# OpenRing_PPG.net
KiCad netlist of a schematic drawn in Altium Designer
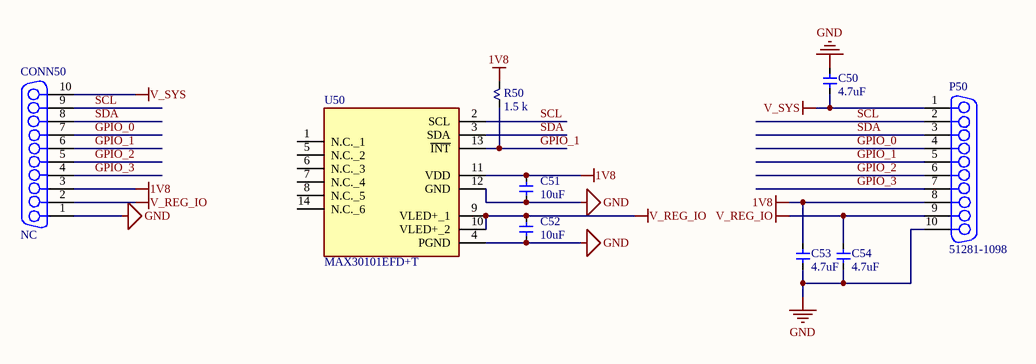
[diagram p0: OpenRing_PPG.SchDoc]

(export (version "E")
  (design (tool "Eeschema 10.0.6"))
  (components
    (comp (ref "C50")
      (value "4.7uF")
      (footprint "CAPC1005X05N")
      (description "Multilayer Ceramic Capacitor, 4.7 uF, 10 V, ± 20%, X5R, 0402 [1005 Metric]")
      (fields
        (field (name "MANUFACTURER") "Murata")
        (field (name "MANUFACTURER PART NUMBER") "GRM155R61A475MEAAD")
      )
      (libsource (lib "OpenRingComponents") (part "GRM155R61A475MEAAD"))
    )
    (comp (ref "C51")
      (value "10uF")
      (footprint "CAPC1005X05N")
      (description "Multilayer Ceramic Capacitor, 10 uF, 10 V, ± 20%, X5R, 0402 [1005 Metric]")
      (fields
        (field (name "MANUFACTURER") "Samsung")
        (field (name "MANUFACTURER PART NUMBER") "CL05A106MP5NUNC")
      )
      (libsource (lib "OpenRingComponents") (part "CL05A106MP5NUNC"))
    )
    (comp (ref "C52")
      (value "10uF")
      (footprint "CAPC1005X05N")
      (description "Multilayer Ceramic Capacitor, 10 uF, 10 V, ± 20%, X5R, 0402 [1005 Metric]")
      (fields
        (field (name "MANUFACTURER") "Samsung")
        (field (name "MANUFACTURER PART NUMBER") "CL05A106MP5NUNC")
      )
      (libsource (lib "OpenRingComponents") (part "CL05A106MP5NUNC"))
    )
    (comp (ref "C53")
      (value "4.7uF")
      (footprint "CAPC1005X05N")
      (description "Multilayer Ceramic Capacitor, 4.7 uF, 10 V, ± 20%, X5R, 0402 [1005 Metric]")
      (fields
        (field (name "MANUFACTURER") "Murata")
        (field (name "MANUFACTURER PART NUMBER") "GRM155R61A475MEAAD")
      )
      (libsource (lib "OpenRingComponents") (part "GRM155R61A475MEAAD"))
    )
    (comp (ref "C54")
      (value "4.7uF")
      (footprint "CAPC1005X05N")
      (description "Multilayer Ceramic Capacitor, 4.7 uF, 10 V, ± 20%, X5R, 0402 [1005 Metric]")
      (fields
        (field (name "MANUFACTURER") "Murata")
        (field (name "MANUFACTURER PART NUMBER") "GRM155R61A475MEAAD")
      )
      (libsource (lib "OpenRingComponents") (part "GRM155R61A475MEAAD"))
    )
    (comp (ref "CONN50")
      (value "NC")
      (footprint "51281-1098-PCB")
      (libsource (lib "Connectors") (part "51281-1098-PCB"))
    )
    (comp (ref "P50")
      (value "51281-1098")
      (footprint "51281-1098")
      (description "FFC/FPC Connector, Surface Mount, Right-Angle, Non-ZIF, Dual Contact Style")
      (fields (field (name "MANUFACTURER") "Molex"))
      (libsource (lib "Connectors") (part "51281-1098"))
    )
    (comp (ref "R50")
      (value "1.5 k")
      (footprint "RESC1005X04N")
      (description "RES SMD 1.5K OHM 1% 1/10W 0402")
      (fields
        (field (name "MANUFACTURER") "Panasonic Electronic Components")
        (field (name "MANUFACTURER PART NUMBER") "ERJ-2RKF1501X")
      )
      (libsource (lib "OpenRingComponents") (part "ERJ-2RKF1501X"))
    )
    (comp (ref "U50")
      (value "MAX30101EFD+T")
      (footprint "14-LEAD-OESIP")
      (description "High-Sensitivity Pulse Oximeter and Heart-Rate Sensor for Fitness & Healthcare")
      (fields (field (name "MANUFACTURER") "Maxim"))
      (libsource (lib "Modules") (part "MAX30101EFD+T"))
    )
  )
  (nets
    (net (code "1") (name "/GPIO_0") (class "Default")
      (node (ref "CONN50") (pin "7") (pinfunction "7_7") (pintype "passive"))
      (node (ref "P50") (pin "4") (pinfunction "4_4") (pintype "passive"))
    )
    (net (code "2") (name "/GPIO_1") (class "Default")
      (node (ref "CONN50") (pin "6") (pinfunction "6_6") (pintype "passive"))
      (node (ref "P50") (pin "5") (pinfunction "5_5") (pintype "passive"))
      (node (ref "R50") (pin "1") (pinfunction "1_1") (pintype "passive"))
      (node (ref "U50") (pin "13") (pinfunction "~{INT}_13") (pintype "passive"))
    )
    (net (code "3") (name "/GPIO_2") (class "Default")
      (node (ref "CONN50") (pin "5") (pinfunction "5_5") (pintype "passive"))
      (node (ref "P50") (pin "6") (pinfunction "6_6") (pintype "passive"))
    )
    (net (code "4") (name "/GPIO_3") (class "Default")
      (node (ref "CONN50") (pin "4") (pinfunction "4_4") (pintype "passive"))
      (node (ref "P50") (pin "7") (pinfunction "7_7") (pintype "passive"))
    )
    (net (code "5") (name "/SCL") (class "Default")
      (node (ref "CONN50") (pin "9") (pinfunction "9_9") (pintype "passive"))
      (node (ref "P50") (pin "2") (pinfunction "2_2") (pintype "passive"))
      (node (ref "U50") (pin "2") (pinfunction "SCL_2") (pintype "passive"))
    )
    (net (code "6") (name "/SDA") (class "Default")
      (node (ref "CONN50") (pin "8") (pinfunction "8_8") (pintype "passive"))
      (node (ref "P50") (pin "3") (pinfunction "3_3") (pintype "passive"))
      (node (ref "U50") (pin "3") (pinfunction "SDA_3") (pintype "passive"))
    )
    (net (code "7") (name "1V8") (class "Default")
      (node (ref "C51") (pin "2") (pinfunction "2_2") (pintype "passive"))
      (node (ref "C53") (pin "2") (pinfunction "2_2") (pintype "passive"))
      (node (ref "CONN50") (pin "3") (pinfunction "3_3") (pintype "passive"))
      (node (ref "P50") (pin "8") (pinfunction "8_8") (pintype "passive"))
      (node (ref "R50") (pin "2") (pinfunction "2_2") (pintype "passive"))
      (node (ref "U50") (pin "11") (pinfunction "VDD_11") (pintype "passive"))
    )
    (net (code "8") (name "GND") (class "Default")
      (node (ref "C50") (pin "2") (pinfunction "2_2") (pintype "passive"))
      (node (ref "C51") (pin "1") (pinfunction "1_1") (pintype "passive"))
      (node (ref "C52") (pin "2") (pinfunction "2_2") (pintype "passive"))
      (node (ref "C53") (pin "1") (pinfunction "1_1") (pintype "passive"))
      (node (ref "C54") (pin "1") (pinfunction "1_1") (pintype "passive"))
      (node (ref "CONN50") (pin "1") (pinfunction "1_1") (pintype "passive"))
      (node (ref "P50") (pin "10") (pinfunction "10_10") (pintype "passive"))
      (node (ref "U50") (pin "12") (pinfunction "GND_12") (pintype "passive"))
      (node (ref "U50") (pin "4") (pinfunction "PGND_4") (pintype "passive"))
    )
    (net (code "9") (name "V_REG_IO") (class "Default")
      (node (ref "C52") (pin "1") (pinfunction "1_1") (pintype "passive"))
      (node (ref "C54") (pin "2") (pinfunction "2_2") (pintype "passive"))
      (node (ref "CONN50") (pin "2") (pinfunction "2_2") (pintype "passive"))
      (node (ref "P50") (pin "9") (pinfunction "9_9") (pintype "passive"))
      (node (ref "U50") (pin "10") (pinfunction "VLED+_2_10") (pintype "passive"))
      (node (ref "U50") (pin "9") (pinfunction "VLED+_1_9") (pintype "passive"))
    )
    (net (code "10") (name "V_SYS") (class "Default")
      (node (ref "C50") (pin "1") (pinfunction "1_1") (pintype "passive"))
      (node (ref "CONN50") (pin "10") (pinfunction "10_10") (pintype "passive"))
      (node (ref "P50") (pin "1") (pinfunction "1_1") (pintype "passive"))
    )
    (net (code "11") (name "unconnected-(U50-N.C._1-Pad1)") (class "Default")
      (node (ref "U50") (pin "1") (pinfunction "N.C._1_1") (pintype "passive"))
    )
    (net (code "12") (name "unconnected-(U50-N.C._2-Pad5)") (class "Default")
      (node (ref "U50") (pin "5") (pinfunction "N.C._2_5") (pintype "passive"))
    )
    (net (code "13") (name "unconnected-(U50-N.C._3-Pad6)") (class "Default")
      (node (ref "U50") (pin "6") (pinfunction "N.C._3_6") (pintype "passive"))
    )
    (net (code "14") (name "unconnected-(U50-N.C._4-Pad7)") (class "Default")
      (node (ref "U50") (pin "7") (pinfunction "N.C._4_7") (pintype "passive"))
    )
    (net (code "15") (name "unconnected-(U50-N.C._5-Pad8)") (class "Default")
      (node (ref "U50") (pin "8") (pinfunction "N.C._5_8") (pintype "passive"))
    )
    (net (code "16") (name "unconnected-(U50-N.C._6-Pad14)") (class "Default")
      (node (ref "U50") (pin "14") (pinfunction "N.C._6_14") (pintype "passive"))
    )
  )
)
